# pi-pots.net
KiCad netlist of a schematic drawn in EAGLE
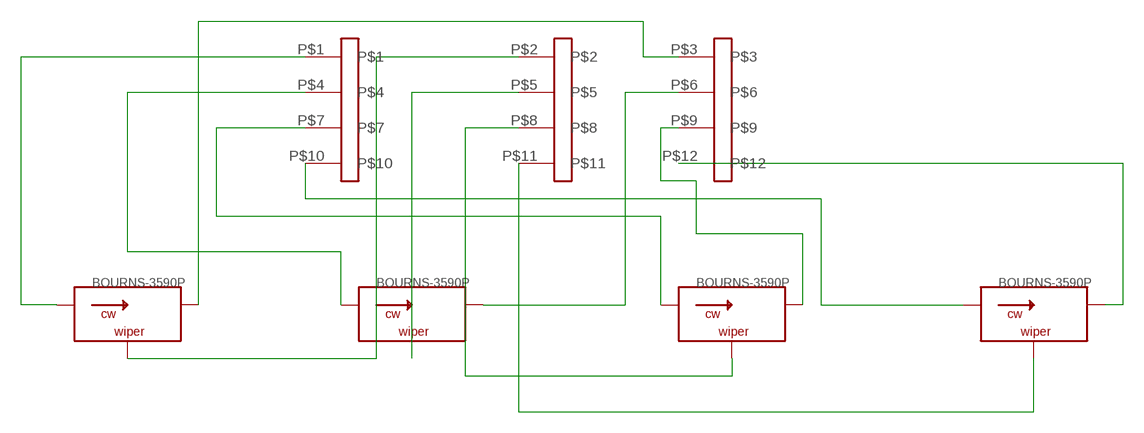
[diagram p0: schematic, sheet 1]

(export (version "E")
  (design (tool "Eeschema 10.0.6"))
  (components
    (comp (ref "I_GAIN")
      (value "BOURNS-3590P")
      (footprint "eagle-import:3590P")
      (fields (field (name "PARTNO") "3590P-1-103L-ND"))
      (libsource (lib "eagle-import") (part "BOURNS-3590P"))
    )
    (comp (ref "J1")
      (value "PINHD-3X4")
      (footprint "eagle-import:3X04")
      (fields (field (name "PARTNO") "952-2121-ND (2x)"))
      (libsource (lib "eagle-import") (part "PINHD-3X4"))
    )
    (comp (ref "OUTPUT_OFFSET")
      (value "BOURNS-3590P")
      (footprint "eagle-import:3590P")
      (fields (field (name "PARTNO") "3590P-1-103L-ND"))
      (libsource (lib "eagle-import") (part "BOURNS-3590P"))
    )
    (comp (ref "P_GAIN")
      (value "BOURNS-3590P")
      (footprint "eagle-import:3590P")
      (fields (field (name "PARTNO") "3590P-1-103L-ND"))
      (libsource (lib "eagle-import") (part "BOURNS-3590P"))
    )
    (comp (ref "SWEEP_AMP")
      (value "BOURNS-3590P")
      (footprint "eagle-import:3590P")
      (fields (field (name "PARTNO") "3590P-1-103L-ND"))
      (libsource (lib "eagle-import") (part "BOURNS-3590P"))
    )
  )
  (nets
    (net (code "1") (name "Net-(I_GAIN-P$1)") (class "Default")
      (node (ref "I_GAIN") (pin "1") (pinfunction "P$1_1") (pintype "bidirectional"))
      (node (ref "J1") (pin "P$4") (pinfunction "P$4_P$4") (pintype "bidirectional"))
    )
    (net (code "2") (name "Net-(I_GAIN-P$2)") (class "Default")
      (node (ref "I_GAIN") (pin "2") (pinfunction "P$2_2") (pintype "bidirectional"))
      (node (ref "J1") (pin "P$5") (pinfunction "P$5_P$5") (pintype "bidirectional"))
    )
    (net (code "3") (name "Net-(I_GAIN-P$3)") (class "Default")
      (node (ref "I_GAIN") (pin "3") (pinfunction "P$3_3") (pintype "bidirectional"))
      (node (ref "J1") (pin "P$6") (pinfunction "P$6_P$6") (pintype "bidirectional"))
    )
    (net (code "4") (name "Net-(OUTPUT_OFFSET-P$1)") (class "Default")
      (node (ref "J1") (pin "P$7") (pinfunction "P$7_P$7") (pintype "bidirectional"))
      (node (ref "OUTPUT_OFFSET") (pin "1") (pinfunction "P$1_1") (pintype "bidirectional"))
    )
    (net (code "5") (name "Net-(OUTPUT_OFFSET-P$2)") (class "Default")
      (node (ref "J1") (pin "P$8") (pinfunction "P$8_P$8") (pintype "bidirectional"))
      (node (ref "OUTPUT_OFFSET") (pin "2") (pinfunction "P$2_2") (pintype "bidirectional"))
    )
    (net (code "6") (name "Net-(OUTPUT_OFFSET-P$3)") (class "Default")
      (node (ref "J1") (pin "P$9") (pinfunction "P$9_P$9") (pintype "bidirectional"))
      (node (ref "OUTPUT_OFFSET") (pin "3") (pinfunction "P$3_3") (pintype "bidirectional"))
    )
    (net (code "7") (name "Net-(P_GAIN-P$1)") (class "Default")
      (node (ref "J1") (pin "P$1") (pinfunction "P$1_P$1") (pintype "bidirectional"))
      (node (ref "P_GAIN") (pin "1") (pinfunction "P$1_1") (pintype "bidirectional"))
    )
    (net (code "8") (name "Net-(P_GAIN-P$2)") (class "Default")
      (node (ref "J1") (pin "P$2") (pinfunction "P$2_P$2") (pintype "bidirectional"))
      (node (ref "P_GAIN") (pin "2") (pinfunction "P$2_2") (pintype "bidirectional"))
    )
    (net (code "9") (name "Net-(P_GAIN-P$3)") (class "Default")
      (node (ref "J1") (pin "P$3") (pinfunction "P$3_P$3") (pintype "bidirectional"))
      (node (ref "P_GAIN") (pin "3") (pinfunction "P$3_3") (pintype "bidirectional"))
    )
    (net (code "10") (name "Net-(SWEEP_AMP-P$1)") (class "Default")
      (node (ref "J1") (pin "P$10") (pinfunction "P$10_P$10") (pintype "bidirectional"))
      (node (ref "SWEEP_AMP") (pin "1") (pinfunction "P$1_1") (pintype "bidirectional"))
    )
    (net (code "11") (name "Net-(SWEEP_AMP-P$2)") (class "Default")
      (node (ref "J1") (pin "P$11") (pinfunction "P$11_P$11") (pintype "bidirectional"))
      (node (ref "SWEEP_AMP") (pin "2") (pinfunction "P$2_2") (pintype "bidirectional"))
    )
    (net (code "12") (name "Net-(SWEEP_AMP-P$3)") (class "Default")
      (node (ref "J1") (pin "P$12") (pinfunction "P$12_P$12") (pintype "bidirectional"))
      (node (ref "SWEEP_AMP") (pin "3") (pinfunction "P$3_3") (pintype "bidirectional"))
    )
  )
)
